# 4_Configuration.net
KiCad netlist of a schematic drawn in Altium Designer
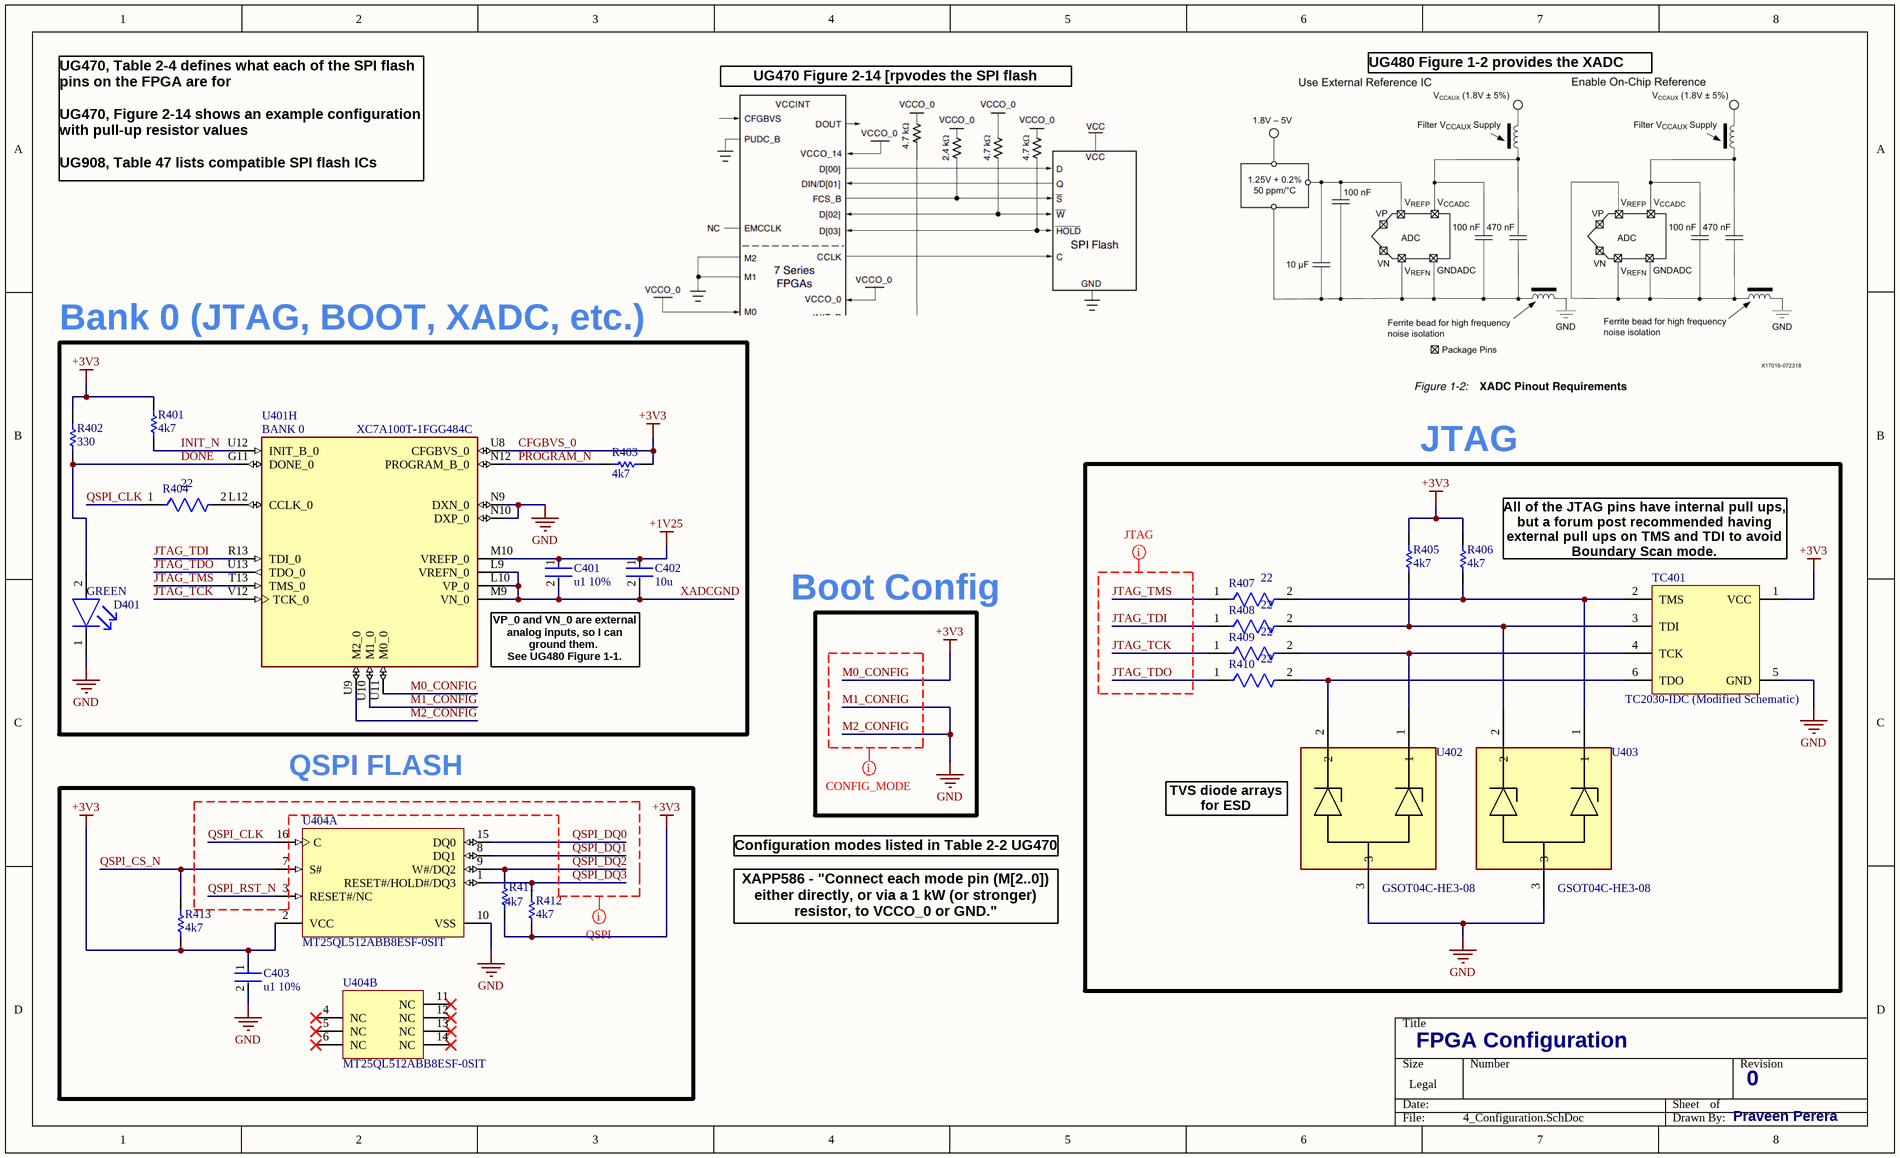
[diagram p0: 4_Configuration.SchDoc]

(export (version "E")
  (design (tool "Eeschema 10.0.6"))
  (components
    (comp (ref "C401")
      (value "u1 10%")
      (footprint "FP-CL891-IPC_C")
      (description "CL05B104KB5NNNC\r\n\r\nCap Ceramic 100nF 50V X7R ±10% SMD 0402 +125°C Paper T/R")
      (libsource (lib "Altium Content Vault") (part "b4654b650e69147ec39a6b967a45e02"))
    )
    (comp (ref "C402")
      (value "10u")
      (footprint "FP-CL05A106MP5NUNC-MFG")
      (description "CL05A106MP5NUNC\r\n\r\nCAP CER 10UF 10V X5R 0402")
      (fields
        (field (name "OCTOPART") "https://octopart.com/cl05a106mp5nunc-samsung-22457395")
        (field (name "TOLERANCE") "20%")
      )
      (libsource (lib "Altium Content Vault") (part "b4654b650e69147ec39a6b967a45e02"))
    )
    (comp (ref "C403")
      (value "u1 10%")
      (footprint "FP-CL891-IPC_C")
      (description "CL05B104KB5NNNC\r\n\r\nCap Ceramic 100nF 50V X7R ±10% SMD 0402 +125°C Paper T/R")
      (libsource (lib "Altium Content Vault") (part "b4654b650e69147ec39a6b967a45e02"))
    )
    (comp (ref "D401")
      (value "GREEN")
      (footprint "FP-SML-D12-MFG")
      (description "SML-D12M1WT86\r\n\r\nLED YLW/GREEN DIFFUSED 1608 SMD")
      (fields (field (name "MANUFACTURER PART NUMBER") "SML-D12M1WT86") (field (name "MANUFACTURER") "Rohm"))
      (libsource (lib "Altium Content Vault") (part "8706943c75ba83719d021d2fdc84c58"))
    )
    (comp (ref "R401")
      (value "4k7")
      (footprint "RESC0603X28X15NL05T05")
      (description "CRCW02014K70FNED")
      (fields (field (name "MANUFACTURER") "Vishay Dale"))
      (libsource (lib "Altium Content Vault") (part "RES"))
    )
    (comp (ref "R402")
      (value "330")
      (footprint "RESC0201(0603)_M")
      (description "330R 0.05W 5% 0201 (0603 Metric)  SMD")
      (fields (field (name "TOLERANCE") "5 %") (field (name "POWER") "0.05 W"))
      (libsource (lib "Altium Content Vault") (part "RES"))
    )
    (comp (ref "R403")
      (value "4k7")
      (footprint "RESC0603X28X15NL05T05")
      (description "CRCW02014K70FNED")
      (fields (field (name "MANUFACTURER") "Vishay Dale"))
      (libsource (lib "Altium Content Vault") (part "RES"))
    )
    (comp (ref "R404")
      (value "22")
      (footprint "FP-RMCF0201-IPC_C")
      (description "RMCF0201JG22R0\r\n\r\n22Ω ±5% 0.05W 0201 Thick Film Chip Resistor AEC-Q200 compliant")
      (fields (field (name "TOLERANCE") "5%"))
      (libsource (lib "Altium Content Vault") (part "1029c3af85768c4190bb7ad29bc67b5"))
    )
    (comp (ref "R405")
      (value "4k7")
      (footprint "RESC0603X28X15NL05T05")
      (description "CRCW02014K70FNED")
      (fields (field (name "MANUFACTURER") "Vishay Dale"))
      (libsource (lib "Altium Content Vault") (part "RES"))
    )
    (comp (ref "R406")
      (value "4k7")
      (footprint "RESC0603X28X15NL05T05")
      (description "CRCW02014K70FNED")
      (fields (field (name "MANUFACTURER") "Vishay Dale"))
      (libsource (lib "Altium Content Vault") (part "RES"))
    )
    (comp (ref "R407")
      (value "22")
      (footprint "FP-RMCF0201-IPC_C")
      (description "RMCF0201JG22R0\r\n\r\n22Ω ±5% 0.05W 0201 Thick Film Chip Resistor AEC-Q200 compliant")
      (fields (field (name "TOLERANCE") "5%"))
      (libsource (lib "Altium Content Vault") (part "1029c3af85768c4190bb7ad29bc67b5"))
    )
    (comp (ref "R408")
      (value "22")
      (footprint "FP-RMCF0201-IPC_C")
      (description "RMCF0201JG22R0\r\n\r\n22Ω ±5% 0.05W 0201 Thick Film Chip Resistor AEC-Q200 compliant")
      (fields (field (name "TOLERANCE") "5%"))
      (libsource (lib "Altium Content Vault") (part "1029c3af85768c4190bb7ad29bc67b5"))
    )
    (comp (ref "R409")
      (value "22")
      (footprint "FP-RMCF0201-IPC_C")
      (description "RMCF0201JG22R0\r\n\r\n22Ω ±5% 0.05W 0201 Thick Film Chip Resistor AEC-Q200 compliant")
      (fields (field (name "TOLERANCE") "5%"))
      (libsource (lib "Altium Content Vault") (part "1029c3af85768c4190bb7ad29bc67b5"))
    )
    (comp (ref "R410")
      (value "22")
      (footprint "FP-RMCF0201-IPC_C")
      (description "RMCF0201JG22R0\r\n\r\n22Ω ±5% 0.05W 0201 Thick Film Chip Resistor AEC-Q200 compliant")
      (fields (field (name "TOLERANCE") "5%"))
      (libsource (lib "Altium Content Vault") (part "1029c3af85768c4190bb7ad29bc67b5"))
    )
    (comp (ref "R411")
      (value "4k7")
      (footprint "RESC0603X28X15NL05T05")
      (description "CRCW02014K70FNED")
      (fields (field (name "MANUFACTURER") "Vishay Dale"))
      (libsource (lib "Altium Content Vault") (part "RES"))
    )
    (comp (ref "R412")
      (value "4k7")
      (footprint "RESC0603X28X15NL05T05")
      (description "CRCW02014K70FNED")
      (fields (field (name "MANUFACTURER") "Vishay Dale"))
      (libsource (lib "Altium Content Vault") (part "RES"))
    )
    (comp (ref "R413")
      (value "4k7")
      (footprint "RESC0603X28X15NL05T05")
      (description "CRCW02014K70FNED")
      (fields (field (name "MANUFACTURER") "Vishay Dale"))
      (libsource (lib "Altium Content Vault") (part "RES"))
    )
    (comp (ref "TC401")
      (value "TC2030-IDC (Modified Schematic)")
      (footprint "*TC2030-IDC")
      (description "PLUG-OF-NAILS 6-PIN W/ LEGS 8")
      (fields (field (name "MF") "Tag-Connect LLC") (field (name "MP") "TC2030-IDC"))
      (libsource (lib "Withanage Perera") (part "TC2030-IDC"))
    )
    (comp (ref "U401")
      (value "XC7A100T-1FGG484C")
      (footprint "BGA484C100P22X22_2300X2300X260N")
      (description "Artix-7 Field Programmable Gate Array (FPGA) IC 285 4976640 101440 484-BBGA")
      (fields (field (name "MF") "Xilinx Inc."))
      (libsource (lib "XC7A100T-1FGG484C - Modified") (part "XC7A100T-1FGG484C"))
    )
    (comp (ref "U402")
      (value "GSOT04C-HE3-08")
      (footprint "SOT_C-HE3-08_VIS")
      (description "ESD PROTECTION DIODE SOT23")
      (fields (field (name "COPYRIGHT") "Copyright (C) 2025 Ultra Librarian. All rights reserved."))
      (libsource (lib "GSOT04C-HE3-08") (part "GSOT04C-HE3-08"))
    )
    (comp (ref "U403")
      (value "GSOT04C-HE3-08")
      (footprint "SOT_C-HE3-08_VIS")
      (description "ESD PROTECTION DIODE SOT23")
      (fields (field (name "COPYRIGHT") "Copyright (C) 2025 Ultra Librarian. All rights reserved."))
      (libsource (lib "GSOT04C-HE3-08") (part "GSOT04C-HE3-08"))
    )
    (comp (ref "U404")
      (value "MT25QL512ABB8ESF-0SIT")
      (footprint "MICT-SF-16_L")
      (description "Micron Serial NOR Flash Memory, 512 Mbits, 2.7 to 3.6 V, -40 to 85 degC, 16-Pin SOP2 (SF), RoHS")
      (fields (field (name "MANUFACTURER") "Micron"))
      (libsource (lib "Altium Content Vault") (part "MICT-MT25QL512ABB-SOP2-16"))
    )
  )
  (nets
    (net (code "1") (name "+1V25") (class "Default")
      (node (ref "C401") (pin "1") (pinfunction "1_1") (pintype "passive"))
      (node (ref "C402") (pin "1") (pinfunction "1_1") (pintype "passive"))
      (node (ref "U401") (pin "M10") (pinfunction "VREFP_0_M10") (pintype "power_in"))
    )
    (net (code "2") (name "+3V3") (class "Default")
      (node (ref "C403") (pin "1") (pinfunction "1_1") (pintype "passive"))
      (node (ref "R401") (pin "2") (pinfunction "2_2") (pintype "passive"))
      (node (ref "R402") (pin "1") (pinfunction "1_1") (pintype "passive"))
      (node (ref "R403") (pin "1") (pinfunction "1_1") (pintype "passive"))
      (node (ref "R405") (pin "2") (pinfunction "2_2") (pintype "passive"))
      (node (ref "R406") (pin "2") (pinfunction "2_2") (pintype "passive"))
      (node (ref "R411") (pin "1") (pinfunction "1_1") (pintype "passive"))
      (node (ref "R412") (pin "1") (pinfunction "1_1") (pintype "passive"))
      (node (ref "R413") (pin "1") (pinfunction "1_1") (pintype "passive"))
      (node (ref "TC401") (pin "1") (pinfunction "VCC_1") (pintype "passive"))
      (node (ref "U401") (pin "U11") (pinfunction "M0_0_U11") (pintype "bidirectional"))
      (node (ref "U401") (pin "U8") (pinfunction "CFGBVS_0_U8") (pintype "bidirectional"))
      (node (ref "U404") (pin "2") (pinfunction "VCC_2") (pintype "power_in"))
    )
    (net (code "3") (name "/DONE") (class "Default")
      (node (ref "D401") (pin "2") (pinfunction "A_2") (pintype "passive"))
      (node (ref "R402") (pin "2") (pinfunction "2_2") (pintype "passive"))
      (node (ref "U401") (pin "G11") (pinfunction "DONE_0_G11") (pintype "bidirectional"))
    )
    (net (code "4") (name "/INIT_N") (class "Default")
      (node (ref "R401") (pin "1") (pinfunction "1_1") (pintype "passive"))
      (node (ref "U401") (pin "U12") (pinfunction "INIT_B_0_U12") (pintype "input"))
    )
    (net (code "5") (name "/JTAG_TCK") (class "Default")
      (node (ref "R409") (pin "1") (pinfunction "1_1") (pintype "passive"))
      (node (ref "U401") (pin "V12") (pinfunction "TCK_0_V12") (pintype "input"))
    )
    (net (code "6") (name "/JTAG_TDI") (class "Default")
      (node (ref "R408") (pin "1") (pinfunction "1_1") (pintype "passive"))
      (node (ref "U401") (pin "R13") (pinfunction "TDI_0_R13") (pintype "input"))
    )
    (net (code "7") (name "/JTAG_TDO") (class "Default")
      (node (ref "R410") (pin "1") (pinfunction "1_1") (pintype "passive"))
      (node (ref "U401") (pin "U13") (pinfunction "TDO_0_U13") (pintype "output"))
    )
    (net (code "8") (name "/JTAG_TMS") (class "Default")
      (node (ref "R407") (pin "1") (pinfunction "1_1") (pintype "passive"))
      (node (ref "U401") (pin "T13") (pinfunction "TMS_0_T13") (pintype "input"))
    )
    (net (code "9") (name "/PROGRAM_N") (class "Default")
      (node (ref "R403") (pin "2") (pinfunction "2_2") (pintype "passive"))
      (node (ref "U401") (pin "N12") (pinfunction "PROGRAM_B_0_N12") (pintype "bidirectional"))
    )
    (net (code "10") (name "/QSPI_CLK") (class "Default")
      (node (ref "R404") (pin "1") (pinfunction "1_1") (pintype "passive"))
      (node (ref "U404") (pin "16") (pinfunction "C_16") (pintype "input"))
    )
    (net (code "11") (name "/QSPI_CS_N") (class "Default")
      (node (ref "R413") (pin "2") (pinfunction "2_2") (pintype "passive"))
      (node (ref "U404") (pin "7") (pinfunction "S#_7") (pintype "input"))
    )
    (net (code "12") (name "/QSPI_DQ0") (class "Default")
      (node (ref "U404") (pin "15") (pinfunction "DQ0_15") (pintype "bidirectional"))
    )
    (net (code "13") (name "/QSPI_DQ1") (class "Default")
      (node (ref "U404") (pin "8") (pinfunction "DQ1_8") (pintype "bidirectional"))
    )
    (net (code "14") (name "/QSPI_DQ2") (class "Default")
      (node (ref "R411") (pin "2") (pinfunction "2_2") (pintype "passive"))
      (node (ref "U404") (pin "9") (pinfunction "W#/DQ2_9") (pintype "bidirectional"))
    )
    (net (code "15") (name "/QSPI_DQ3") (class "Default")
      (node (ref "R412") (pin "2") (pinfunction "2_2") (pintype "passive"))
      (node (ref "U404") (pin "1") (pinfunction "RESET#/HOLD#/DQ3_1") (pintype "bidirectional"))
    )
    (net (code "16") (name "/QSPI_RST_N") (class "Default")
      (node (ref "U404") (pin "3") (pinfunction "RESET#/NC_3") (pintype "input"))
    )
    (net (code "17") (name "/XADCGND") (class "Default")
      (node (ref "C401") (pin "2") (pinfunction "2_2") (pintype "passive"))
      (node (ref "C402") (pin "2") (pinfunction "2_2") (pintype "passive"))
      (node (ref "U401") (pin "L10") (pinfunction "VP_0_L10") (pintype "power_in"))
      (node (ref "U401") (pin "L9") (pinfunction "VREFN_0_L9") (pintype "power_in"))
      (node (ref "U401") (pin "M9") (pinfunction "VN_0_M9") (pintype "power_in"))
    )
    (net (code "18") (name "GND") (class "Default")
      (node (ref "C403") (pin "2") (pinfunction "2_2") (pintype "passive"))
      (node (ref "D401") (pin "1") (pinfunction "C_1") (pintype "passive"))
      (node (ref "TC401") (pin "5") (pinfunction "GND_5") (pintype "passive"))
      (node (ref "U401") (pin "N10") (pinfunction "DXP_0_N10") (pintype "bidirectional"))
      (node (ref "U401") (pin "N9") (pinfunction "DXN_0_N9") (pintype "bidirectional"))
      (node (ref "U401") (pin "U10") (pinfunction "M1_0_U10") (pintype "bidirectional"))
      (node (ref "U401") (pin "U9") (pinfunction "M2_0_U9") (pintype "bidirectional"))
      (node (ref "U402") (pin "3") (pinfunction "3_3") (pintype "passive"))
      (node (ref "U403") (pin "3") (pinfunction "3_3") (pintype "passive"))
      (node (ref "U404") (pin "10") (pinfunction "VSS_10") (pintype "power_in"))
    )
    (net (code "19") (name "Net-(TC401-TCK)") (class "Default")
      (node (ref "R409") (pin "2") (pinfunction "2_2") (pintype "passive"))
      (node (ref "TC401") (pin "4") (pinfunction "TCK_4") (pintype "passive"))
      (node (ref "U402") (pin "1") (pinfunction "1_1") (pintype "passive"))
    )
    (net (code "20") (name "Net-(TC401-TDI)") (class "Default")
      (node (ref "R405") (pin "1") (pinfunction "1_1") (pintype "passive"))
      (node (ref "R408") (pin "2") (pinfunction "2_2") (pintype "passive"))
      (node (ref "TC401") (pin "3") (pinfunction "TDI_3") (pintype "passive"))
      (node (ref "U403") (pin "2") (pinfunction "2_2") (pintype "passive"))
    )
    (net (code "21") (name "Net-(TC401-TDO)") (class "Default")
      (node (ref "R410") (pin "2") (pinfunction "2_2") (pintype "passive"))
      (node (ref "TC401") (pin "6") (pinfunction "TDO_6") (pintype "passive"))
      (node (ref "U402") (pin "2") (pinfunction "2_2") (pintype "passive"))
    )
    (net (code "22") (name "Net-(TC401-TMS)") (class "Default")
      (node (ref "R406") (pin "1") (pinfunction "1_1") (pintype "passive"))
      (node (ref "R407") (pin "2") (pinfunction "2_2") (pintype "passive"))
      (node (ref "TC401") (pin "2") (pinfunction "TMS_2") (pintype "passive"))
      (node (ref "U403") (pin "1") (pinfunction "1_1") (pintype "passive"))
    )
    (net (code "23") (name "Net-(U401H-CCLK_0)") (class "Default")
      (node (ref "R404") (pin "2") (pinfunction "2_2") (pintype "passive"))
      (node (ref "U401") (pin "L12") (pinfunction "CCLK_0_L12") (pintype "bidirectional"))
    )
    (net (code "24") (name "unconnected-(U404B-NC-Pad4)") (class "Default")
      (node (ref "U404") (pin "4") (pinfunction "NC_4") (pintype "passive+no_connect"))
    )
    (net (code "25") (name "unconnected-(U404B-NC-Pad5)") (class "Default")
      (node (ref "U404") (pin "5") (pinfunction "NC_5") (pintype "passive+no_connect"))
    )
    (net (code "26") (name "unconnected-(U404B-NC-Pad6)") (class "Default")
      (node (ref "U404") (pin "6") (pinfunction "NC_6") (pintype "passive+no_connect"))
    )
    (net (code "27") (name "unconnected-(U404B-NC-Pad11)") (class "Default")
      (node (ref "U404") (pin "11") (pinfunction "NC_11") (pintype "passive+no_connect"))
    )
    (net (code "28") (name "unconnected-(U404B-NC-Pad12)") (class "Default")
      (node (ref "U404") (pin "12") (pinfunction "NC_12") (pintype "passive+no_connect"))
    )
    (net (code "29") (name "unconnected-(U404B-NC-Pad13)") (class "Default")
      (node (ref "U404") (pin "13") (pinfunction "NC_13") (pintype "passive+no_connect"))
    )
    (net (code "30") (name "unconnected-(U404B-NC-Pad14)") (class "Default")
      (node (ref "U404") (pin "14") (pinfunction "NC_14") (pintype "passive+no_connect"))
    )
  )
)
